# MCU_CAN.net
KiCad netlist of a schematic drawn in Altium Designer
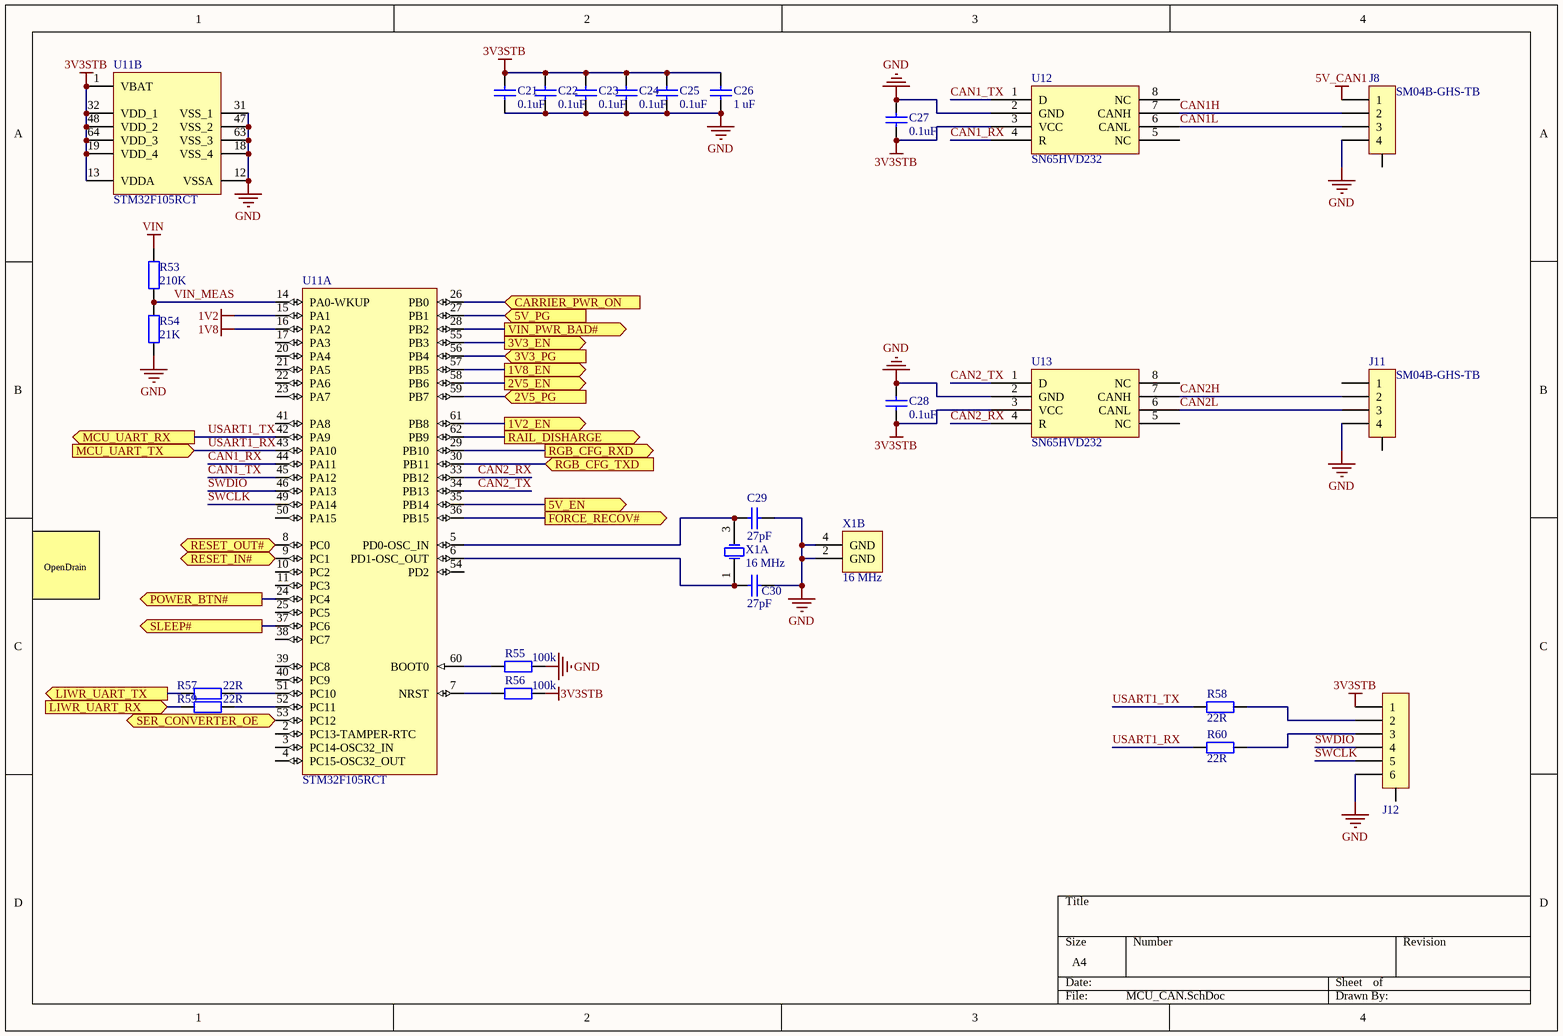
[diagram p0: MCU_CAN.SchDoc]

(export (version "E")
  (design (tool "Eeschema 10.0.6"))
  (components
    (comp (ref "C21")
      (value "GRM155R71C104KA88D")
      (footprint "0402C_M")
      (description "CAP CER 0.1UF 16V X7R 0402")
      (fields
        (field (name "MANUFACTURER") "Murata Electronics North America")
        (field (name "TOLERANCE") "±10%")
        (field (name "CAPACITANCE") "0.1uF")
      )
      (libsource (lib "KMTI-main") (part "GRM155R71C104KA88D"))
    )
    (comp (ref "C22")
      (value "GRM155R71C104KA88D")
      (footprint "0402C_M")
      (description "CAP CER 0.1UF 16V X7R 0402")
      (fields
        (field (name "MANUFACTURER") "Murata Electronics North America")
        (field (name "TOLERANCE") "±10%")
        (field (name "CAPACITANCE") "0.1uF")
      )
      (libsource (lib "KMTI-main") (part "GRM155R71C104KA88D"))
    )
    (comp (ref "C23")
      (value "GRM155R71C104KA88D")
      (footprint "0402C_M")
      (description "CAP CER 0.1UF 16V X7R 0402")
      (fields
        (field (name "MANUFACTURER") "Murata Electronics North America")
        (field (name "TOLERANCE") "±10%")
        (field (name "CAPACITANCE") "0.1uF")
      )
      (libsource (lib "KMTI-main") (part "GRM155R71C104KA88D"))
    )
    (comp (ref "C24")
      (value "GRM155R71C104KA88D")
      (footprint "0402C_M")
      (description "CAP CER 0.1UF 16V X7R 0402")
      (fields
        (field (name "MANUFACTURER") "Murata Electronics North America")
        (field (name "TOLERANCE") "±10%")
        (field (name "CAPACITANCE") "0.1uF")
      )
      (libsource (lib "KMTI-main") (part "GRM155R71C104KA88D"))
    )
    (comp (ref "C25")
      (value "GRM155R71C104KA88D")
      (footprint "0402C_M")
      (description "CAP CER 0.1UF 16V X7R 0402")
      (fields
        (field (name "MANUFACTURER") "Murata Electronics North America")
        (field (name "TOLERANCE") "±10%")
        (field (name "CAPACITANCE") "0.1uF")
      )
      (libsource (lib "KMTI-main") (part "GRM155R71C104KA88D"))
    )
    (comp (ref "C26")
      (value "GRM188R61A105KA61D")
      (footprint "0603C_M")
      (description "CAP CER 1UF 10V X5R 0603")
      (fields
        (field (name "MANUFACTURER") "Murata")
        (field (name "TOLERANCE") "10 %")
        (field (name "CAPACITANCE") "1 uF")
      )
      (libsource (lib "KMTI-main") (part "GRM188R61A105KA61D"))
    )
    (comp (ref "C27")
      (value "GRM155R71C104KA88D")
      (footprint "0402C_M")
      (description "CAP CER 0.1UF 16V X7R 0402")
      (fields
        (field (name "MANUFACTURER") "Murata Electronics North America")
        (field (name "TOLERANCE") "±10%")
        (field (name "CAPACITANCE") "0.1uF")
      )
      (libsource (lib "KMTI-main") (part "GRM155R71C104KA88D"))
    )
    (comp (ref "C28")
      (value "GRM155R71C104KA88D")
      (footprint "0402C_M")
      (description "CAP CER 0.1UF 16V X7R 0402")
      (fields
        (field (name "MANUFACTURER") "Murata Electronics North America")
        (field (name "TOLERANCE") "±10%")
        (field (name "CAPACITANCE") "0.1uF")
      )
      (libsource (lib "KMTI-main") (part "GRM155R71C104KA88D"))
    )
    (comp (ref "C29")
      (value "GRM1555C1H270JA01D")
      (footprint "0402C_M")
      (description "Cap Ceramic 27pF 50V C0G 5% SMD 0402 125C T/R")
      (fields (field (name "MANUFACTURER") "Murata") (field (name "CAPACITANCE") "27pF"))
      (libsource (lib "KMTI-main") (part "GRM1555C1H270JA01D"))
    )
    (comp (ref "C30")
      (value "GRM1555C1H270JA01D")
      (footprint "0402C_M")
      (description "Cap Ceramic 27pF 50V C0G 5% SMD 0402 125C T/R")
      (fields (field (name "MANUFACTURER") "Murata") (field (name "CAPACITANCE") "27pF"))
      (libsource (lib "KMTI-main") (part "GRM1555C1H270JA01D"))
    )
    (comp (ref "J8")
      (value "SM04B-GHS-TB")
      (footprint "SM04B-GHS-TB")
      (description "CONN HEADER GH SIDE 4POS 1.25MM")
      (fields
        (field (name "MANUFACTURER") "JST Sales America Inc.")
        (field (name "MANUFACTURER PART NUMBER") "SM04B-GHS-TB(LF)(SN)-")
      )
      (libsource (lib "KMTI-main") (part "SM04B-GHS-TB(LF)(SN)-"))
    )
    (comp (ref "J11")
      (value "SM04B-GHS-TB")
      (footprint "SM04B-GHS-TB")
      (description "CONN HEADER GH SIDE 4POS 1.25MM")
      (fields
        (field (name "MANUFACTURER") "JST Sales America Inc.")
        (field (name "MANUFACTURER PART NUMBER") "SM04B-GHS-TB(LF)(SN)-")
      )
      (libsource (lib "KMTI-main") (part "SM04B-GHS-TB(LF)(SN)-"))
    )
    (comp (ref "J12")
      (value "SM06B-SRSS-TB(LF)(SN)")
      (footprint "SM06B-SRSS-TB")
      (description "CONN HEADER SH 6POS SIDE 1MM TIN")
      (fields (field (name "MANUFACTURER") "JST Sales America Inc."))
      (libsource (lib "KMTI-main") (part "SM06B-SRSS-TB(LF)(SN)"))
    )
    (comp (ref "R53")
      (value "210K")
      (footprint "0402R_M")
      (description "RES SMD 210K OHM 1% 1/16W 0402")
      (fields
        (field (name "MANUFACTURER") "Vishay Dale")
        (field (name "MANUFACTURER PART NUMBER") "CRCW0402210KFKED")
      )
      (libsource (lib "KMTI-main") (part "CRCW0402210KFKED"))
    )
    (comp (ref "R54")
      (value "21K")
      (footprint "0402R_M")
      (description "RES SMD 21K OHM 1% 1/16W 0402")
      (fields
        (field (name "MANUFACTURER") "Vishay Dale")
        (field (name "MANUFACTURER PART NUMBER") "CRCW040221K0FKED")
      )
      (libsource (lib "KMTI-main") (part "CRCW040221K0FKED"))
    )
    (comp (ref "R55")
      (value "CRCW0402100KJNED")
      (footprint "0402R_M")
      (description "RES SMD 100K OHM 5% 1/16W 0402")
      (fields
        (field (name "MANUFACTURER") "Vishay")
        (field (name "TOLERANCE") "5 %")
        (field (name "RESISTANCE") "100k")
      )
      (libsource (lib "KMTI-main") (part "CRCW0402100KJNED"))
    )
    (comp (ref "R56")
      (value "CRCW0402100KJNED")
      (footprint "0402R_M")
      (description "RES SMD 100K OHM 5% 1/16W 0402")
      (fields
        (field (name "MANUFACTURER") "Vishay")
        (field (name "TOLERANCE") "5 %")
        (field (name "RESISTANCE") "100k")
      )
      (libsource (lib "KMTI-main") (part "CRCW0402100KJNED"))
    )
    (comp (ref "R57")
      (value "CRCW040222R0JNED")
      (footprint "0402R_M")
      (description "RES SMD 22 OHM 5% 1/16W 0402")
      (fields
        (field (name "MANUFACTURER") "Vishay / Dale")
        (field (name "TOLERANCE") "5 %")
        (field (name "RESISTANCE") "22R")
      )
      (libsource (lib "KMTI-main") (part "CRCW040222R0JNED"))
    )
    (comp (ref "R58")
      (value "CRCW040222R0JNED")
      (footprint "0402R_M")
      (description "RES SMD 22 OHM 5% 1/16W 0402")
      (fields
        (field (name "MANUFACTURER") "Vishay / Dale")
        (field (name "RESISTANCE") "22R")
        (field (name "TOLERANCE") "5 %")
      )
      (libsource (lib "KMTI-main") (part "CRCW040222R0JNED"))
    )
    (comp (ref "R59")
      (value "CRCW040222R0JNED")
      (footprint "0402R_M")
      (description "RES SMD 22 OHM 5% 1/16W 0402")
      (fields
        (field (name "MANUFACTURER") "Vishay / Dale")
        (field (name "TOLERANCE") "5 %")
        (field (name "RESISTANCE") "22R")
      )
      (libsource (lib "KMTI-main") (part "CRCW040222R0JNED"))
    )
    (comp (ref "R60")
      (value "CRCW040222R0JNED")
      (footprint "0402R_M")
      (description "RES SMD 22 OHM 5% 1/16W 0402")
      (fields
        (field (name "MANUFACTURER") "Vishay / Dale")
        (field (name "RESISTANCE") "22R")
        (field (name "TOLERANCE") "5 %")
      )
      (libsource (lib "KMTI-main") (part "CRCW040222R0JNED"))
    )
    (comp (ref "U11")
      (value "STM32F105RCT")
      (footprint "LQFP64_LD")
      (fields
        (field (name "MANUFACTURER") "STMicroelectronics")
        (field (name "MANUFACTURER PART NUMBER") "STM32F105RCT6TR")
      )
      (libsource (lib "KMTI-main") (part "STM32F105RCT"))
    )
    (comp (ref "U12")
      (value "SN65HVD232")
      (footprint "SOIC8_L")
      (description "IC 3.3V CAN TXRX 8-SOIC")
      (fields
        (field (name "MANUFACTURER") "Texas Instruments")
        (field (name "MANUFACTURER PART NUMBER") "SN65HVD232QDRQ1")
      )
      (libsource (lib "KMTI-main") (part "SN65HVD232QDRQ1"))
    )
    (comp (ref "U13")
      (value "SN65HVD232")
      (footprint "SOIC8_L")
      (description "IC 3.3V CAN TXRX 8-SOIC")
      (fields
        (field (name "MANUFACTURER") "Texas Instruments")
        (field (name "MANUFACTURER PART NUMBER") "SN65HVD232QDRQ1")
      )
      (libsource (lib "KMTI-main") (part "SN65HVD232QDRQ1"))
    )
    (comp (ref "X1")
      (value "CRYS 16MHz 9pF")
      (footprint "TSX-3225_H")
      (description "Crystals 16MHz 10ppm 9pF -20C +75C")
      (fields
        (field (name "MANUFACTURER") "Epson Timing")
        (field (name "MANUFACTURER PART NUMBER") "TSX-3225 16.0000MF09Z-AC3")
        (field (name "FREQUENCY") "16 MHz")
      )
      (libsource (lib "") (part "TSX-3225 16.0000MF09Z-AC3_1"))
    )
  )
  (nets
    (net (code "1") (name "/1V2_EN") (class "Default")
      (node (ref "U11") (pin "61") (pinfunction "PB8_61") (pintype "bidirectional"))
    )
    (net (code "2") (name "/1V8_EN") (class "Default")
      (node (ref "U11") (pin "57") (pinfunction "PB5_57") (pintype "bidirectional"))
    )
    (net (code "3") (name "/2V5_EN") (class "Default")
      (node (ref "U11") (pin "58") (pinfunction "PB6_58") (pintype "bidirectional"))
    )
    (net (code "4") (name "/2V5_PG") (class "Default")
      (node (ref "U11") (pin "59") (pinfunction "PB7_59") (pintype "bidirectional"))
    )
    (net (code "5") (name "/3V3_EN") (class "Default")
      (node (ref "U11") (pin "55") (pinfunction "PB3_55") (pintype "bidirectional"))
    )
    (net (code "6") (name "/3V3_PG") (class "Default")
      (node (ref "U11") (pin "56") (pinfunction "PB4_56") (pintype "bidirectional"))
    )
    (net (code "7") (name "/5V_EN") (class "Default")
      (node (ref "U11") (pin "35") (pinfunction "PB14_35") (pintype "bidirectional"))
    )
    (net (code "8") (name "/5V_PG") (class "Default")
      (node (ref "U11") (pin "27") (pinfunction "PB1_27") (pintype "bidirectional"))
    )
    (net (code "9") (name "/CAN1H") (class "Default")
      (node (ref "J8") (pin "2") (pinfunction "2_2") (pintype "passive"))
      (node (ref "U12") (pin "7") (pinfunction "CANH_7") (pintype "passive"))
    )
    (net (code "10") (name "/CAN1L") (class "Default")
      (node (ref "J8") (pin "3") (pinfunction "3_3") (pintype "passive"))
      (node (ref "U12") (pin "6") (pinfunction "CANL_6") (pintype "passive"))
    )
    (net (code "11") (name "/CAN1_RX") (class "Default")
      (node (ref "U11") (pin "44") (pinfunction "PA11_44") (pintype "bidirectional"))
      (node (ref "U12") (pin "4") (pinfunction "R_4") (pintype "passive"))
    )
    (net (code "12") (name "/CAN1_TX") (class "Default")
      (node (ref "U11") (pin "45") (pinfunction "PA12_45") (pintype "bidirectional"))
      (node (ref "U12") (pin "1") (pinfunction "D_1") (pintype "passive"))
    )
    (net (code "13") (name "/CAN2H") (class "Default")
      (node (ref "J11") (pin "2") (pinfunction "2_2") (pintype "passive"))
      (node (ref "U13") (pin "7") (pinfunction "CANH_7") (pintype "passive"))
    )
    (net (code "14") (name "/CAN2L") (class "Default")
      (node (ref "J11") (pin "3") (pinfunction "3_3") (pintype "passive"))
      (node (ref "U13") (pin "6") (pinfunction "CANL_6") (pintype "passive"))
    )
    (net (code "15") (name "/CAN2_RX") (class "Default")
      (node (ref "U11") (pin "33") (pinfunction "PB12_33") (pintype "bidirectional"))
      (node (ref "U13") (pin "4") (pinfunction "R_4") (pintype "passive"))
    )
    (net (code "16") (name "/CAN2_TX") (class "Default")
      (node (ref "U11") (pin "34") (pinfunction "PB13_34") (pintype "bidirectional"))
      (node (ref "U13") (pin "1") (pinfunction "D_1") (pintype "passive"))
    )
    (net (code "17") (name "/CARRIER_PWR_ON") (class "Default")
      (node (ref "U11") (pin "26") (pinfunction "PB0_26") (pintype "bidirectional"))
    )
    (net (code "18") (name "/FORCE_RECOV#") (class "Default")
      (node (ref "U11") (pin "36") (pinfunction "PB15_36") (pintype "bidirectional"))
    )
    (net (code "19") (name "/LIWR_UART_RX") (class "Default")
      (node (ref "R59") (pin "1") (pinfunction "1_1") (pintype "passive"))
    )
    (net (code "20") (name "/LIWR_UART_TX") (class "Default")
      (node (ref "R57") (pin "1") (pinfunction "1_1") (pintype "passive"))
    )
    (net (code "21") (name "/POWER_BTN#") (class "Default")
      (node (ref "U11") (pin "24") (pinfunction "PC4_24") (pintype "bidirectional"))
    )
    (net (code "22") (name "/RAIL_DISHARGE") (class "Default")
      (node (ref "U11") (pin "62") (pinfunction "PB9_62") (pintype "bidirectional"))
    )
    (net (code "23") (name "/RESET_IN#") (class "Default")
      (node (ref "U11") (pin "9") (pinfunction "PC1_9") (pintype "bidirectional"))
    )
    (net (code "24") (name "/RESET_OUT#") (class "Default")
      (node (ref "U11") (pin "8") (pinfunction "PC0_8") (pintype "bidirectional"))
    )
    (net (code "25") (name "/RGB_CFG_RXD") (class "Default")
      (node (ref "U11") (pin "29") (pinfunction "PB10_29") (pintype "bidirectional"))
    )
    (net (code "26") (name "/RGB_CFG_TXD") (class "Default")
      (node (ref "U11") (pin "30") (pinfunction "PB11_30") (pintype "bidirectional"))
    )
    (net (code "27") (name "/SER_CONVERTER_OE") (class "Default")
      (node (ref "U11") (pin "53") (pinfunction "PC12_53") (pintype "bidirectional"))
    )
    (net (code "28") (name "/SLEEP#") (class "Default")
      (node (ref "U11") (pin "37") (pinfunction "PC6_37") (pintype "bidirectional"))
    )
    (net (code "29") (name "/SWCLK") (class "Default")
      (node (ref "J12") (pin "5") (pinfunction "5_5") (pintype "passive"))
      (node (ref "U11") (pin "49") (pinfunction "PA14_49") (pintype "bidirectional"))
    )
    (net (code "30") (name "/SWDIO") (class "Default")
      (node (ref "J12") (pin "4") (pinfunction "4_4") (pintype "passive"))
      (node (ref "U11") (pin "46") (pinfunction "PA13_46") (pintype "bidirectional"))
    )
    (net (code "31") (name "/USART1_RX") (class "Default")
      (node (ref "R60") (pin "1") (pinfunction "1_1") (pintype "passive"))
      (node (ref "U11") (pin "43") (pinfunction "PA10_43") (pintype "bidirectional"))
    )
    (net (code "32") (name "/USART1_TX") (class "Default")
      (node (ref "R58") (pin "1") (pinfunction "1_1") (pintype "passive"))
      (node (ref "U11") (pin "42") (pinfunction "PA9_42") (pintype "bidirectional"))
    )
    (net (code "33") (name "/VIN_MEAS") (class "Default")
      (node (ref "R53") (pin "1") (pinfunction "1_1") (pintype "passive"))
      (node (ref "R54") (pin "2") (pinfunction "2_2") (pintype "passive"))
      (node (ref "U11") (pin "14") (pinfunction "PA0-WKUP_14") (pintype "bidirectional"))
    )
    (net (code "34") (name "/VIN_PWR_BAD#") (class "Default")
      (node (ref "U11") (pin "28") (pinfunction "PB2_28") (pintype "bidirectional"))
    )
    (net (code "35") (name "1V2") (class "Default")
      (node (ref "U11") (pin "15") (pinfunction "PA1_15") (pintype "bidirectional"))
    )
    (net (code "36") (name "1V8") (class "Default")
      (node (ref "U11") (pin "16") (pinfunction "PA2_16") (pintype "bidirectional"))
    )
    (net (code "37") (name "3V3STB") (class "Default")
      (node (ref "C21") (pin "2") (pinfunction "2_2") (pintype "passive"))
      (node (ref "C22") (pin "2") (pinfunction "2_2") (pintype "passive"))
      (node (ref "C23") (pin "2") (pinfunction "2_2") (pintype "passive"))
      (node (ref "C24") (pin "2") (pinfunction "2_2") (pintype "passive"))
      (node (ref "C25") (pin "2") (pinfunction "2_2") (pintype "passive"))
      (node (ref "C26") (pin "2") (pinfunction "2_2") (pintype "passive"))
      (node (ref "C27") (pin "1") (pinfunction "1_1") (pintype "passive"))
      (node (ref "C28") (pin "1") (pinfunction "1_1") (pintype "passive"))
      (node (ref "J12") (pin "1") (pinfunction "1_1") (pintype "passive"))
      (node (ref "R56") (pin "2") (pinfunction "2_2") (pintype "passive"))
      (node (ref "U11") (pin "1") (pinfunction "VBAT_1") (pintype "power_in"))
      (node (ref "U11") (pin "13") (pinfunction "VDDA_13") (pintype "power_in"))
      (node (ref "U11") (pin "19") (pinfunction "VDD_4_19") (pintype "power_in"))
      (node (ref "U11") (pin "32") (pinfunction "VDD_1_32") (pintype "power_in"))
      (node (ref "U11") (pin "48") (pinfunction "VDD_2_48") (pintype "power_in"))
      (node (ref "U11") (pin "64") (pinfunction "VDD_3_64") (pintype "power_in"))
      (node (ref "U12") (pin "3") (pinfunction "VCC_3") (pintype "passive"))
      (node (ref "U13") (pin "3") (pinfunction "VCC_3") (pintype "passive"))
    )
    (net (code "38") (name "5V_CAN1") (class "Default")
      (node (ref "J8") (pin "1") (pinfunction "1_1") (pintype "passive"))
    )
    (net (code "39") (name "GND") (class "Default")
      (node (ref "C21") (pin "1") (pinfunction "1_1") (pintype "passive"))
      (node (ref "C22") (pin "1") (pinfunction "1_1") (pintype "passive"))
      (node (ref "C23") (pin "1") (pinfunction "1_1") (pintype "passive"))
      (node (ref "C24") (pin "1") (pinfunction "1_1") (pintype "passive"))
      (node (ref "C25") (pin "1") (pinfunction "1_1") (pintype "passive"))
      (node (ref "C26") (pin "1") (pinfunction "1_1") (pintype "passive"))
      (node (ref "C27") (pin "2") (pinfunction "2_2") (pintype "passive"))
      (node (ref "C28") (pin "2") (pinfunction "2_2") (pintype "passive"))
      (node (ref "C29") (pin "2") (pinfunction "2_2") (pintype "passive"))
      (node (ref "C30") (pin "2") (pinfunction "2_2") (pintype "passive"))
      (node (ref "J11") (pin "4") (pinfunction "4_4") (pintype "passive"))
      (node (ref "J12") (pin "6") (pinfunction "6_6") (pintype "passive"))
      (node (ref "J8") (pin "4") (pinfunction "4_4") (pintype "passive"))
      (node (ref "R54") (pin "1") (pinfunction "1_1") (pintype "passive"))
      (node (ref "R55") (pin "2") (pinfunction "2_2") (pintype "passive"))
      (node (ref "U11") (pin "12") (pinfunction "VSSA_12") (pintype "power_in"))
      (node (ref "U11") (pin "18") (pinfunction "VSS_4_18") (pintype "power_in"))
      (node (ref "U11") (pin "31") (pinfunction "VSS_1_31") (pintype "power_in"))
      (node (ref "U11") (pin "47") (pinfunction "VSS_2_47") (pintype "power_in"))
      (node (ref "U11") (pin "63") (pinfunction "VSS_3_63") (pintype "power_in"))
      (node (ref "U12") (pin "2") (pinfunction "GND_2") (pintype "passive"))
      (node (ref "U13") (pin "2") (pinfunction "GND_2") (pintype "passive"))
      (node (ref "X1") (pin "2") (pinfunction "GND_2") (pintype "power_in"))
      (node (ref "X1") (pin "4") (pinfunction "GND_4") (pintype "power_in"))
    )
    (net (code "40") (name "Net-(J12-Pad2)") (class "Default")
      (node (ref "J12") (pin "2") (pinfunction "2_2") (pintype "passive"))
      (node (ref "R58") (pin "2") (pinfunction "2_2") (pintype "passive"))
    )
    (net (code "41") (name "Net-(J12-Pad3)") (class "Default")
      (node (ref "J12") (pin "3") (pinfunction "3_3") (pintype "passive"))
      (node (ref "R60") (pin "2") (pinfunction "2_2") (pintype "passive"))
    )
    (net (code "42") (name "Net-(U11A-BOOT0)") (class "Default")
      (node (ref "R55") (pin "1") (pinfunction "1_1") (pintype "passive"))
      (node (ref "U11") (pin "60") (pinfunction "BOOT0_60") (pintype "input"))
    )
    (net (code "43") (name "Net-(U11A-NRST)") (class "Default")
      (node (ref "R56") (pin "1") (pinfunction "1_1") (pintype "passive"))
      (node (ref "U11") (pin "7") (pinfunction "NRST_7") (pintype "bidirectional"))
    )
    (net (code "44") (name "Net-(U11A-PC10)") (class "Default")
      (node (ref "R57") (pin "2") (pinfunction "2_2") (pintype "passive"))
      (node (ref "U11") (pin "51") (pinfunction "PC10_51") (pintype "bidirectional"))
    )
    (net (code "45") (name "Net-(U11A-PC11)") (class "Default")
      (node (ref "R59") (pin "2") (pinfunction "2_2") (pintype "passive"))
      (node (ref "U11") (pin "52") (pinfunction "PC11_52") (pintype "bidirectional"))
    )
    (net (code "46") (name "Net-(U11A-PD0-OSC_IN)") (class "Default")
      (node (ref "C29") (pin "1") (pinfunction "1_1") (pintype "passive"))
      (node (ref "U11") (pin "5") (pinfunction "PD0-OSC_IN_5") (pintype "bidirectional"))
      (node (ref "X1") (pin "3") (pinfunction "X2_3") (pintype "passive"))
    )
    (net (code "47") (name "Net-(U11A-PD1-OSC_OUT)") (class "Default")
      (node (ref "C30") (pin "1") (pinfunction "1_1") (pintype "passive"))
      (node (ref "U11") (pin "6") (pinfunction "PD1-OSC_OUT_6") (pintype "bidirectional"))
      (node (ref "X1") (pin "1") (pinfunction "X1_1") (pintype "passive"))
    )
    (net (code "48") (name "VIN") (class "Default")
      (node (ref "R53") (pin "2") (pinfunction "2_2") (pintype "passive"))
    )
    (net (code "49") (name "unconnected-(J8-Pad0)") (class "Default")
      (node (ref "J8") (pin "0") (pinfunction "0_0") (pintype "passive"))
    )
    (net (code "50") (name "unconnected-(J11-Pad0)") (class "Default")
      (node (ref "J11") (pin "0") (pinfunction "0_0") (pintype "passive"))
    )
    (net (code "51") (name "unconnected-(J11-Pad1)") (class "Default")
      (node (ref "J11") (pin "1") (pinfunction "1_1") (pintype "passive"))
    )
    (net (code "52") (name "unconnected-(J12-Pad0)") (class "Default")
      (node (ref "J12") (pin "0") (pinfunction "0_0") (pintype "passive"))
    )
    (net (code "53") (name "unconnected-(U11A-PA3-Pad17)") (class "Default")
      (node (ref "U11") (pin "17") (pinfunction "PA3_17") (pintype "bidirectional"))
    )
    (net (code "54") (name "unconnected-(U11A-PA4-Pad20)") (class "Default")
      (node (ref "U11") (pin "20") (pinfunction "PA4_20") (pintype "bidirectional"))
    )
    (net (code "55") (name "unconnected-(U11A-PA5-Pad21)") (class "Default")
      (node (ref "U11") (pin "21") (pinfunction "PA5_21") (pintype "bidirectional"))
    )
    (net (code "56") (name "unconnected-(U11A-PA6-Pad22)") (class "Default")
      (node (ref "U11") (pin "22") (pinfunction "PA6_22") (pintype "bidirectional"))
    )
    (net (code "57") (name "unconnected-(U11A-PA7-Pad23)") (class "Default")
      (node (ref "U11") (pin "23") (pinfunction "PA7_23") (pintype "bidirectional"))
    )
    (net (code "58") (name "unconnected-(U11A-PA8-Pad41)") (class "Default")
      (node (ref "U11") (pin "41") (pinfunction "PA8_41") (pintype "bidirectional"))
    )
    (net (code "59") (name "unconnected-(U11A-PA15-Pad50)") (class "Default")
      (node (ref "U11") (pin "50") (pinfunction "PA15_50") (pintype "bidirectional"))
    )
    (net (code "60") (name "unconnected-(U11A-PC2-Pad10)") (class "Default")
      (node (ref "U11") (pin "10") (pinfunction "PC2_10") (pintype "bidirectional"))
    )
    (net (code "61") (name "unconnected-(U11A-PC3-Pad11)") (class "Default")
      (node (ref "U11") (pin "11") (pinfunction "PC3_11") (pintype "bidirectional"))
    )
    (net (code "62") (name "unconnected-(U11A-PC5-Pad25)") (class "Default")
      (node (ref "U11") (pin "25") (pinfunction "PC5_25") (pintype "bidirectional"))
    )
    (net (code "63") (name "unconnected-(U11A-PC7-Pad38)") (class "Default")
      (node (ref "U11") (pin "38") (pinfunction "PC7_38") (pintype "bidirectional"))
    )
    (net (code "64") (name "unconnected-(U11A-PC8-Pad39)") (class "Default")
      (node (ref "U11") (pin "39") (pinfunction "PC8_39") (pintype "bidirectional"))
    )
    (net (code "65") (name "unconnected-(U11A-PC9-Pad40)") (class "Default")
      (node (ref "U11") (pin "40") (pinfunction "PC9_40") (pintype "bidirectional"))
    )
    (net (code "66") (name "unconnected-(U11A-PC13-TAMPER-RTC-Pad2)") (class "Default")
      (node (ref "U11") (pin "2") (pinfunction "PC13-TAMPER-RTC_2") (pintype "bidirectional"))
    )
    (net (code "67") (name "unconnected-(U11A-PC14-OSC32_IN-Pad3)") (class "Default")
      (node (ref "U11") (pin "3") (pinfunction "PC14-OSC32_IN_3") (pintype "bidirectional"))
    )
    (net (code "68") (name "unconnected-(U11A-PC15-OSC32_OUT-Pad4)") (class "Default")
      (node (ref "U11") (pin "4") (pinfunction "PC15-OSC32_OUT_4") (pintype "bidirectional"))
    )
    (net (code "69") (name "unconnected-(U11A-PD2-Pad54)") (class "Default")
      (node (ref "U11") (pin "54") (pinfunction "PD2_54") (pintype "bidirectional"))
    )
    (net (code "70") (name "unconnected-(U12-NC-Pad5)") (class "Default")
      (node (ref "U12") (pin "5") (pinfunction "NC_5") (pintype "passive"))
    )
    (net (code "71") (name "unconnected-(U12-NC-Pad8)") (class "Default")
      (node (ref "U12") (pin "8") (pinfunction "NC_8") (pintype "passive"))
    )
    (net (code "72") (name "unconnected-(U13-NC-Pad5)") (class "Default")
      (node (ref "U13") (pin "5") (pinfunction "NC_5") (pintype "passive"))
    )
    (net (code "73") (name "unconnected-(U13-NC-Pad8)") (class "Default")
      (node (ref "U13") (pin "8") (pinfunction "NC_8") (pintype "passive"))
    )
  )
)
